# 3_Buck_Boost_19V.net
KiCad netlist of a schematic drawn in Altium Designer
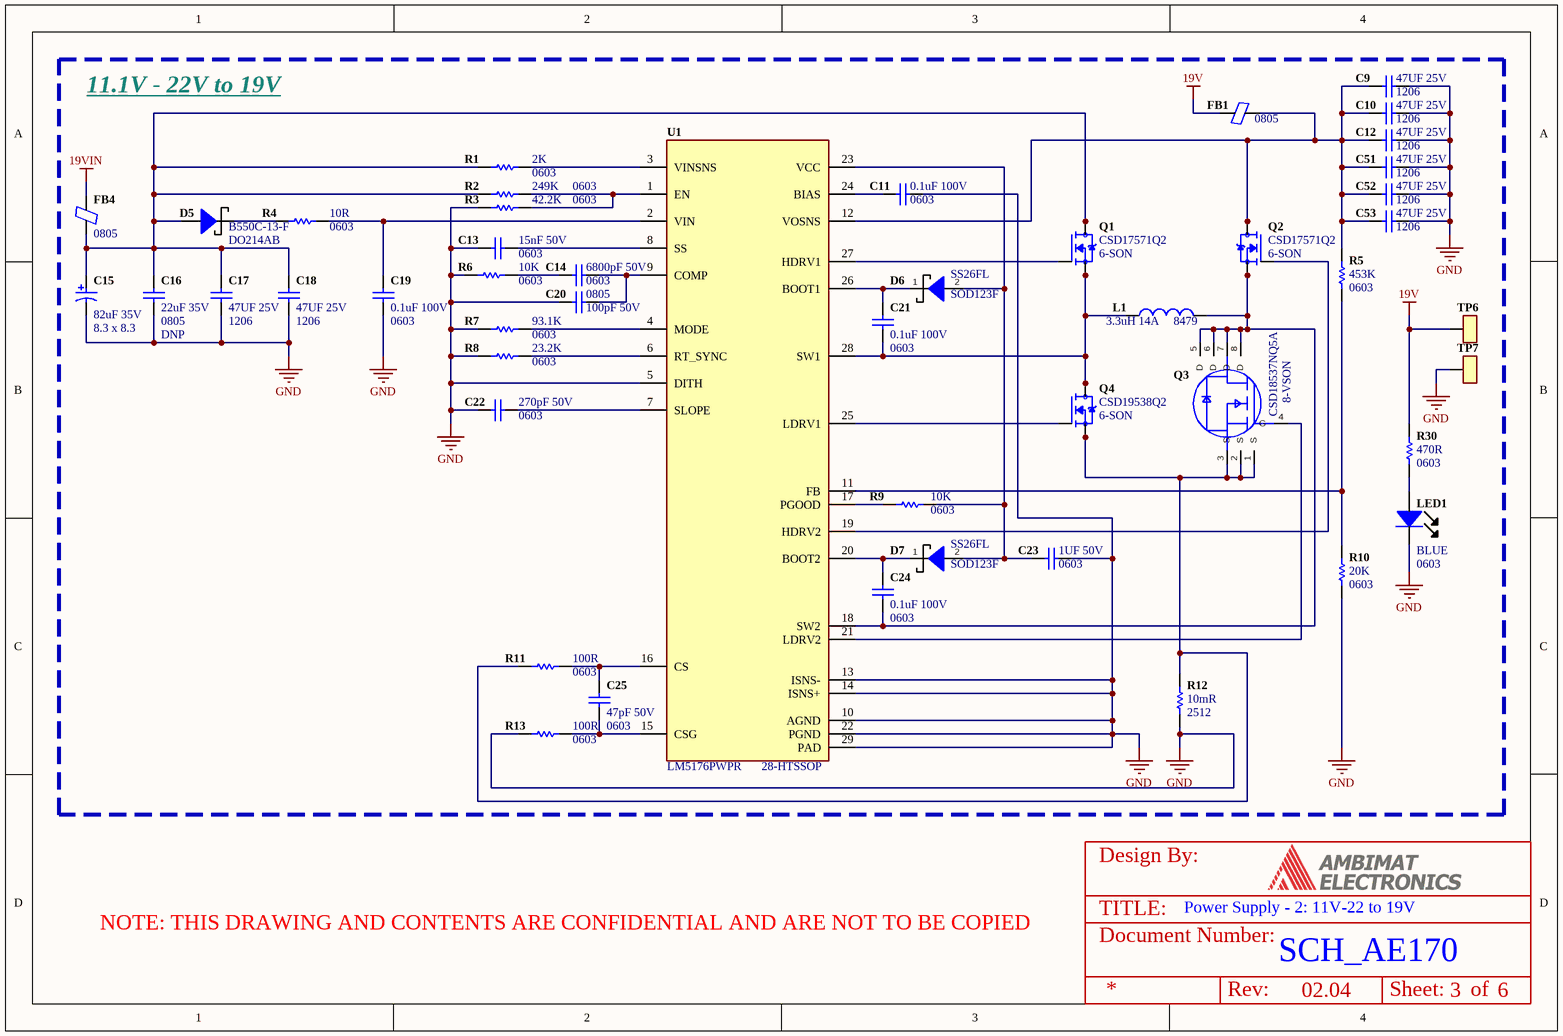
[diagram p0: 3. Buck Boost_19V.SchDoc]

(export (version "E")
  (design (tool "Eeschema 10.0.6"))
  (components
    (comp (ref "C9")
      (value "CAP CER 47UF 25V X5R 1206")
      (footprint "LimLabDL:1206 - NP")
      (fields
        (field (name "MANUFACTURER PART NUMBER") "C3216X5R1E476M160AC")
        (field (name "MANUFACTURER") "TDK Corporation")
        (field (name "VENDOR-1 PART NUMBER") "445-8047-1-ND")
        (field (name "PART NAME") "47UF 25V")
        (field (name "PCB FOOTPRINT") "1206")
      )
      (libsource (lib "LimLabDL") (part "CS47UF-25V1206"))
    )
    (comp (ref "C10")
      (value "CAP CER 47UF 25V X5R 1206")
      (footprint "LimLabDL:1206 - NP")
      (fields
        (field (name "MANUFACTURER PART NUMBER") "C3216X5R1E476M160AC")
        (field (name "MANUFACTURER") "TDK Corporation")
        (field (name "VENDOR-1 PART NUMBER") "445-8047-1-ND")
        (field (name "PART NAME") "47UF 25V")
        (field (name "PCB FOOTPRINT") "1206")
      )
      (libsource (lib "LimLabDL") (part "CS47UF-25V1206"))
    )
    (comp (ref "C11")
      (value "CAP CER 0.1UF 100V X7R 0603")
      (footprint "LimLabDL:0603C")
      (fields
        (field (name "MANU PART NUMBER") "CC0603KRX7R0BB104")
        (field (name "MANUFACTURER") "YAGEO")
        (field (name "PART NAME") "0.1uF 100V")
        (field (name "PCB FOOTPRINT") "0603")
        (field (name "VENDOR-1 PART NUMBER") "311-1523-1-ND")
      )
      (libsource (lib "LimLabDL") (part "CS0.1uF-100V0603"))
    )
    (comp (ref "C12")
      (value "CAP CER 47UF 25V X5R 1206")
      (footprint "LimLabDL:1206 - NP")
      (fields
        (field (name "MANUFACTURER PART NUMBER") "C3216X5R1E476M160AC")
        (field (name "MANUFACTURER") "TDK Corporation")
        (field (name "VENDOR-1 PART NUMBER") "445-8047-1-ND")
        (field (name "PART NAME") "47UF 25V")
        (field (name "PCB FOOTPRINT") "1206")
      )
      (libsource (lib "LimLabDL") (part "CS47UF-25V1206"))
    )
    (comp (ref "C13")
      (value "CAP CER 0.015UF 50V X7R 0603")
      (footprint "LimLabDL:0603C")
      (fields
        (field (name "MANUFACTURER PART NUMBER") "CL10B153KB8NNNC")
        (field (name "MANUFACTURER") "Samsung Electro-Mechanics")
        (field (name "VENDOR-1 PART NUMBER") "1276-1277-1-ND")
        (field (name "PART NAME") "15nF 50V")
        (field (name "PCB FOOTPRINT") "0603")
      )
      (libsource (lib "LimLabDL") (part "CS15nF-50V0603"))
    )
    (comp (ref "C14")
      (value "CAP CER 6800PF 50V X7R 0603")
      (footprint "LimLabDL:0603C")
      (fields
        (field (name "MANUFACTURER") "YAGEO")
        (field (name "VENDOR-1 PART NUMBER") "13-AC0603KPX7R9BB682CT-ND")
        (field (name "PART NAME") "6800pF 50V")
        (field (name "PCB FOOTPRINT") "0603")
        (field (name "MANUFACTURER PART NUMBER") "AC0603KPX7R9BB682")
      )
      (libsource (lib "LimLabDL") (part "CS6800pF-50V0603"))
    )
    (comp (ref "C15")
      (value "CAP ALUM POLY 82UF 20% 35V SMD")
      (footprint "LimLabDL:CAP_PC_8X12_NCH")
      (fields
        (field (name "MANU PART NUMBER") "35SVPF82M")
        (field (name "MANUFACTURER") "Panasonic")
        (field (name "VENDOR-1 PART NUMBER") "P16562CT-ND")
        (field (name "PART NAME") "82uF 35V")
        (field (name "PCB FOOTPRINT") "8.3 x 8.3")
      )
      (libsource (lib "LimLabDL") (part "CS82uF-35VALUM"))
    )
    (comp (ref "C16")
      (value "CAP CER 22UF 35V X5R 0805")
      (footprint "LimLabDL:0805C")
      (fields
        (field (name "MANU PART NUMBER") "C2012X5R1V226M125AC")
        (field (name "MANUFACTURER") "TDK Corporation")
        (field (name "MOUNTING") "DNP")
        (field (name "VENDOR-1 PART NUMBER") "445-14428-1-ND")
        (field (name "PART NAME") "22uF 35V")
        (field (name "PCB FOOTPRINT") "0805")
      )
      (libsource (lib "LimLabDL") (part "CS22uF-35V0805"))
    )
    (comp (ref "C17")
      (value "CAP CER 47UF 25V X5R 1206")
      (footprint "LimLabDL:1206 - NP")
      (fields
        (field (name "MANUFACTURER PART NUMBER") "C3216X5R1E476M160AC")
        (field (name "MANUFACTURER") "TDK Corporation")
        (field (name "VENDOR-1 PART NUMBER") "445-8047-1-ND")
        (field (name "PART NAME") "47UF 25V")
        (field (name "PCB FOOTPRINT") "1206")
      )
      (libsource (lib "LimLabDL") (part "CS47UF-25V1206"))
    )
    (comp (ref "C18")
      (value "CAP CER 47UF 25V X5R 1206")
      (footprint "LimLabDL:1206 - NP")
      (fields
        (field (name "MANUFACTURER PART NUMBER") "C3216X5R1E476M160AC")
        (field (name "MANUFACTURER") "TDK Corporation")
        (field (name "VENDOR-1 PART NUMBER") "445-8047-1-ND")
        (field (name "PART NAME") "47UF 25V")
        (field (name "PCB FOOTPRINT") "1206")
      )
      (libsource (lib "LimLabDL") (part "CS47UF-25V1206"))
    )
    (comp (ref "C19")
      (value "CAP CER 0.1UF 100V X7R 0603")
      (footprint "LimLabDL:0603C")
      (fields
        (field (name "MANU PART NUMBER") "CC0603KRX7R0BB104")
        (field (name "MANUFACTURER") "YAGEO")
        (field (name "PART NAME") "0.1uF 100V")
        (field (name "PCB FOOTPRINT") "0603")
        (field (name "VENDOR-1 PART NUMBER") "311-1523-1-ND")
      )
      (libsource (lib "LimLabDL") (part "CS0.1uF-100V0603"))
    )
    (comp (ref "C20")
      (value "CAP CER 100PF 50V C0G/NP0 0805")
      (footprint "LimLabDL:0805C")
      (fields
        (field (name "MANUFACTURER") "AVX Corporation")
        (field (name "VENDOR-1 PART NUMBER") "478-1316-1-ND")
        (field (name "PART NAME") "100pF 50V")
        (field (name "PCB FOOTPRINT") "0805")
        (field (name "MANU PART NUMBER") "08055A101JAT2A")
      )
      (libsource (lib "LimLabDL") (part "CS100pF-50V0805"))
    )
    (comp (ref "C21")
      (value "CAP CER 0.1UF 100V X7R 0603")
      (footprint "LimLabDL:0603C")
      (fields
        (field (name "MANU PART NUMBER") "CC0603KRX7R0BB104")
        (field (name "MANUFACTURER") "YAGEO")
        (field (name "PART NAME") "0.1uF 100V")
        (field (name "PCB FOOTPRINT") "0603")
        (field (name "VENDOR-1 PART NUMBER") "311-1523-1-ND")
      )
      (libsource (lib "LimLabDL") (part "CS0.1uF-100V0603"))
    )
    (comp (ref "C22")
      (value "CAP CER 270PF 50V X7R 0603")
      (footprint "LimLabDL:0603C")
      (fields
        (field (name "MANUFACTURER PART NUMBER") "CC0603KRX7R9BB271")
        (field (name "MANUFACTURER") "Yageo")
        (field (name "VENDOR-1 PART NUMBER") "311-1185-1-ND")
        (field (name "PART NAME") "270pF 50V")
        (field (name "PCB FOOTPRINT") "0603")
      )
      (libsource (lib "LimLabDL") (part "CS270pF-50V0603"))
    )
    (comp (ref "C23")
      (value "CAP CER 1UF 50V X7R 0603")
      (footprint "LimLabDL:0603C")
      (fields
        (field (name "MANU PART NUMBER") "CC0603KRX7R9BB105")
        (field (name "MANUFACTURER") "Yageo")
        (field (name "PART NAME") "1UF 50V")
        (field (name "PCB FOOTPRINT") "0603")
        (field (name "VENDOR-1 PART NUMBER") "311-2082-1-ND")
      )
      (libsource (lib "LimLabDL") (part "CS1uF-50V0603"))
    )
    (comp (ref "C24")
      (value "CAP CER 0.1UF 100V X7R 0603")
      (footprint "LimLabDL:0603C")
      (fields
        (field (name "MANU PART NUMBER") "CC0603KRX7R0BB104")
        (field (name "MANUFACTURER") "YAGEO")
        (field (name "PART NAME") "0.1uF 100V")
        (field (name "PCB FOOTPRINT") "0603")
        (field (name "VENDOR-1 PART NUMBER") "311-1523-1-ND")
      )
      (libsource (lib "LimLabDL") (part "CS0.1uF-100V0603"))
    )
    (comp (ref "C25")
      (value "CAP CER 47PF 50V X7R 10% 0603")
      (footprint "LimLabDL:0603C")
      (fields
        (field (name "MANUFACTURER") "KEMET")
        (field (name "VENDOR-1 PART NUMBER") "399-16402-1-ND")
        (field (name "PART NAME") "47pF 50V")
        (field (name "PCB FOOTPRINT") "0603")
        (field (name "MANUFACTURER PART NUMBER") "C0603C470K5RAC7867")
      )
      (libsource (lib "LimLabDL") (part "CS47pF-50V0603"))
    )
    (comp (ref "C51")
      (value "CAP CER 47UF 25V X5R 1206")
      (footprint "LimLabDL:1206 - NP")
      (fields
        (field (name "MANUFACTURER PART NUMBER") "C3216X5R1E476M160AC")
        (field (name "MANUFACTURER") "TDK Corporation")
        (field (name "VENDOR-1 PART NUMBER") "445-8047-1-ND")
        (field (name "PART NAME") "47UF 25V")
        (field (name "PCB FOOTPRINT") "1206")
      )
      (libsource (lib "LimLabDL") (part "CS47UF-25V1206"))
    )
    (comp (ref "C52")
      (value "CAP CER 47UF 25V X5R 1206")
      (footprint "LimLabDL:1206 - NP")
      (fields
        (field (name "MANUFACTURER PART NUMBER") "C3216X5R1E476M160AC")
        (field (name "MANUFACTURER") "TDK Corporation")
        (field (name "VENDOR-1 PART NUMBER") "445-8047-1-ND")
        (field (name "PART NAME") "47UF 25V")
        (field (name "PCB FOOTPRINT") "1206")
      )
      (libsource (lib "LimLabDL") (part "CS47UF-25V1206"))
    )
    (comp (ref "C53")
      (value "CAP CER 47UF 25V X5R 1206")
      (footprint "LimLabDL:1206 - NP")
      (fields
        (field (name "MANUFACTURER PART NUMBER") "C3216X5R1E476M160AC")
        (field (name "MANUFACTURER") "TDK Corporation")
        (field (name "VENDOR-1 PART NUMBER") "445-8047-1-ND")
        (field (name "PART NAME") "47UF 25V")
        (field (name "PCB FOOTPRINT") "1206")
      )
      (libsource (lib "LimLabDL") (part "CS47UF-25V1206"))
    )
    (comp (ref "D5")
      (value "DIODE SCHOTTKY 50V 5A SMC")
      (footprint "LimLabDL:DO-214AB-SHKY")
      (fields
        (field (name "MANU PART NUMBER") "B550C-13-F")
        (field (name "MANUFACTURER") "Diodes Incorporated")
        (field (name "VENDOR-1 PART NUMBER") "B550C-FDICT-ND")
        (field (name "PCB FOOTPRINT") "DO214AB")
        (field (name "PART NAME") "B550C-13-F")
      )
      (libsource (lib "LimLabDL") (part "DS-B550C-13-F"))
    )
    (comp (ref "D6")
      (value "DIODE SCHOTTKY 60V 2A SOD123F")
      (footprint "LimLabDL:SOD123F-SHKY")
      (fields
        (field (name "MANU PART NUMBER") "SS26FL")
        (field (name "MANUFACTURER") "onsemi")
        (field (name "VENDOR-1 PART NUMBER") "SS26FLCT-ND")
        (field (name "PCB FOOTPRINT") "SOD123F")
        (field (name "PART NAME") "SS26FL")
      )
      (libsource (lib "LimLabDL") (part "DS-SS26FL"))
    )
    (comp (ref "D7")
      (value "DIODE SCHOTTKY 60V 2A SOD123F")
      (footprint "LimLabDL:SOD123F-SHKY")
      (fields
        (field (name "MANU PART NUMBER") "SS26FL")
        (field (name "MANUFACTURER") "onsemi")
        (field (name "VENDOR-1 PART NUMBER") "SS26FLCT-ND")
        (field (name "PCB FOOTPRINT") "SOD123F")
        (field (name "PART NAME") "SS26FL")
      )
      (libsource (lib "LimLabDL") (part "DS-SS26FL"))
    )
    (comp (ref "FB1")
      (value "FERRITE BEAD 120 OHM 0805 1LN")
      (footprint "LimLabDL:0805F")
      (fields
        (field (name "MANUFACTURER") "Pulse Electronics")
        (field (name "MANUFACTURER PART NUMBER") "ABUP00201209121Y00")
        (field (name "VENDOR-1 PART NUMBER") "553-ABUP00201209121Y00CT-ND")
        (field (name "PCB FOOTPRINT") "0805")
      )
      (libsource (lib "LimLabDL") (part "FB120OHM-0805"))
    )
    (comp (ref "FB4")
      (value "FERRITE BEAD 120 OHM 0805 1LN")
      (footprint "LimLabDL:0805F")
      (fields
        (field (name "MANUFACTURER") "Pulse Electronics")
        (field (name "MANUFACTURER PART NUMBER") "ABUP00201209121Y00")
        (field (name "VENDOR-1 PART NUMBER") "553-ABUP00201209121Y00CT-ND")
        (field (name "PCB FOOTPRINT") "0805")
      )
      (libsource (lib "LimLabDL") (part "FB120OHM-0805"))
    )
    (comp (ref "L1")
      (value "FIXED IND 3.3UH 14A 8.2 MOHM SMD")
      (footprint "LimLabDL:IND_8070-WE")
      (fields
        (field (name "MANUFACTURER PART NUMBER") "7443340330")
        (field (name "MANUFACTURER") "Würth Elektronik")
        (field (name "VENDOR-1 PART NUMBER") "732-2165-1-ND")
        (field (name "PART NAME") "3.3uH 14A")
        (field (name "PCB FOOTPRINT") "8479")
      )
      (libsource (lib "LimLabDL") (part "LS3.3uH14A-8479"))
    )
    (comp (ref "LED1")
      (value "LB Q39G-L2N2-35-1")
      (footprint "LimLabDL:LED0603_BLUE")
      (description "LED BLUE CLEAR 3MM 470NM")
      (fields
        (field (name "MANUFACTURER") "OSRAM Opto Semiconductors Inc")
        (field (name "VENDOR-1 PART NUMBER") "475-2816-1-ND")
        (field (name "PCB FOOTPRINT") "0603")
        (field (name "COLOR") "BLUE")
      )
      (libsource (lib "LimLabDL") (part "LED-BLUE0603"))
    )
    (comp (ref "Q1")
      (value "MOSFET N-CH 30V 22A 6SON")
      (footprint "LimLabDL:CSD17571Q2")
      (fields
        (field (name "MANU PART NUMBER") "CSD17571Q2")
        (field (name "MANUFACTURER") "Texas Instruments")
        (field (name "VENDOR-1 PART NUMBER") "296-37193-1-ND")
        (field (name "PCB FOOTPRINT") "6-SON")
        (field (name "PART NAME") "CSD17571Q2")
      )
      (libsource (lib "LimLabDL") (part "MS-CSD17571Q2"))
    )
    (comp (ref "Q2")
      (value "MOSFET N-CH 30V 22A 6SON")
      (footprint "LimLabDL:CSD17571Q2")
      (fields
        (field (name "MANU PART NUMBER") "CSD17571Q2")
        (field (name "MANUFACTURER") "Texas Instruments")
        (field (name "VENDOR-1 PART NUMBER") "296-37193-1-ND")
        (field (name "PCB FOOTPRINT") "6-SON")
        (field (name "PART NAME") "CSD17571Q2")
      )
      (libsource (lib "LimLabDL") (part "MS-CSD17571Q2"))
    )
    (comp (ref "Q3")
      (value "MOSFET N-CH 60V 50A 8VSON")
      (footprint "LimLabDL:SON127P500X600")
      (fields
        (field (name "MANU PART NUMBER") "CSD18537NQ5A")
        (field (name "MANUFACTURER") "Texas Instruments")
        (field (name "VENDOR-1 PART NUMBER") "296-36455-1-ND")
        (field (name "PCB FOOTPRINT") "8-VSON")
        (field (name "PART NAME") "CSD18537NQ5A")
      )
      (libsource (lib "LimLabDL") (part "MS-CSD18537NQ5A"))
    )
    (comp (ref "Q4")
      (value "MOSFET N-CH 100V 14.4A 6WSON")
      (footprint "LimLabDL:CSD17571Q2")
      (fields
        (field (name "MANU PART NUMBER") "CSD19538Q2")
        (field (name "MANUFACTURER") "Texas Instruments")
        (field (name "VENDOR-1 PART NUMBER") "296-37193-1-ND")
        (field (name "PCB FOOTPRINT") "6-SON")
        (field (name "PART NAME") "CSD19538Q2")
      )
      (libsource (lib "LimLabDL") (part "MS-CSD19538Q2"))
    )
    (comp (ref "R1")
      (value "RS2K-0.1W0603")
      (footprint "LimLabDL:0603")
      (description "RES SMD 2K OHM 5% 1/10W 0603")
      (fields
        (field (name "MANU PART NUMBER") "ERJ-3GEYJ202V")
        (field (name "MANUFACTURER") "Panasonic")
        (field (name "PART NAME") "2K")
        (field (name "PCB FOOTPRINT") "0603")
      )
      (libsource (lib "LimLabDL") (part "RS2K-0.1W0603"))
    )
    (comp (ref "R2")
      (value "RES SMD 249K OHM 1% 1/10W 0603")
      (footprint "LimLabDL:0603")
      (fields
        (field (name "MANUFACTURER PART NUMBER") "AC0603FR-07249KL")
        (field (name "MANUFACTURER") "Yageo")
        (field (name "VENDOR-1 PART NUMBER") "13-AC0603FR-07249KLCT-ND")
        (field (name "PART NAME") "249K")
        (field (name "PCB FOOTPRINT") "0603")
      )
      (libsource (lib "LimLabDL") (part "RS249K-0.1W0603"))
    )
    (comp (ref "R3")
      (value "RES 42.2K OHM 1% 1/10W 0603")
      (footprint "LimLabDL:0603")
      (fields
        (field (name "MANUFACTURER PART NUMBER") "RC0603FR-0742K2L")
        (field (name "MANUFACTURER") "Yageo")
        (field (name "VENDOR-1 PART NUMBER") "311-42.2KHRCT-ND")
        (field (name "PART NAME") "42.2K")
        (field (name "PCB FOOTPRINT") "0603")
      )
      (libsource (lib "LimLabDL") (part "RS42.2K-0.1W0603"))
    )
    (comp (ref "R4")
      (value "RES SMD 10 OHM 1% 1/10W 0603")
      (footprint "LimLabDL:0603")
      (fields
        (field (name "MANU PART NUMBER") "CRCW060310R0FKEA")
        (field (name "MANUFACTURER") "Vishay Dale")
        (field (name "VENDOR-1 PART NUMBER") "541-10.0HCT-ND")
        (field (name "PART NAME") "10R")
        (field (name "PCB FOOTPRINT") "0603")
      )
      (libsource (lib "LimLabDL") (part "RS10R-0.1W0603"))
    )
    (comp (ref "R5")
      (value "RES 453K OHM 1% 1/10W 0603")
      (footprint "LimLabDL:0603")
      (fields
        (field (name "MANU PART NUMBER") "RC0603FR-07453KL")
        (field (name "MANUFACTURER") "Yageo")
        (field (name "VENDOR-1 PART NUMBER") "311-453KHRCT-ND")
        (field (name "PART NAME") "453K")
        (field (name "PCB FOOTPRINT") "0603")
      )
      (libsource (lib "LimLabDL") (part "RS453K-0.1W0603"))
    )
    (comp (ref "R6")
      (value "RES SMD 10K OHM 5% 1/10W 0603")
      (footprint "LimLabDL:0603")
      (fields
        (field (name "MANUFACTURER PART NUMBER") "RC0603JR-0710KL")
        (field (name "MANUFACTURER") "Yageo")
        (field (name "VENDOR-1 PART NUMBER") "311-10KGRCT-ND")
        (field (name "PART NAME") "10K")
        (field (name "PCB FOOTPRINT") "0603")
      )
      (libsource (lib "LimLabDL") (part "RS10K-0.1W0603"))
    )
    (comp (ref "R7")
      (value "RES 93.1K OHM 1% 1/10W 0603")
      (footprint "LimLabDL:0603")
      (fields
        (field (name "MANU PART NUMBER") "RC0603FR-0793K1L")
        (field (name "MANUFACTURER") "YAGEO")
        (field (name "VENDOR-1 PART NUMBER") "311-93.1KHRCT-ND")
        (field (name "PART NAME") "93.1K")
        (field (name "PCB FOOTPRINT") "0603")
      )
      (libsource (lib "LimLabDL") (part "RS93.1K-0.1W0603"))
    )
    (comp (ref "R8")
      (value "RES 23.2K OHM 1% 1/10W 0603")
      (footprint "LimLabDL:0603")
      (fields
        (field (name "MANU PART NUMBER") "RC0603FR-0723K2L")
        (field (name "MANUFACTURER") "YAGEO")
        (field (name "VENDOR-1 PART NUMBER") "311-23.2KHRCT-ND")
        (field (name "PART NAME") "23.2K")
        (field (name "PCB FOOTPRINT") "0603")
      )
      (libsource (lib "LimLabDL") (part "RS23.2K-0.1W0603"))
    )
    (comp (ref "R9")
      (value "RES SMD 10K OHM 5% 1/10W 0603")
      (footprint "LimLabDL:0603")
      (fields
        (field (name "MANUFACTURER") "Yageo")
        (field (name "VENDOR-1 PART NUMBER") "311-10KGRCT-ND")
        (field (name "PCB FOOTPRINT") "0603")
        (field (name "PART NAME") "10K")
        (field (name "MANUFACTURER PART NUMBER") "RC0603JR-0710KL")
      )
      (libsource (lib "LimLabDL") (part "RS10K-0.1W0603"))
    )
    (comp (ref "R10")
      (value "RES SMD 20K OHM 5% 1/10W 0603")
      (footprint "LimLabDL:0603")
      (fields
        (field (name "MANU PART NUMBER") "CRCW060320K0JNEA")
        (field (name "MANUFACTURER") "Vishay Dale")
        (field (name "VENDOR-1 PART NUMBER") "541-20KGCT-ND")
        (field (name "PCB FOOTPRINT") "0603")
        (field (name "PART NAME") "20K")
      )
      (libsource (lib "LimLabDL") (part "RS20K-0.1W0603"))
    )
    (comp (ref "R11")
      (value "RES SMD 100 OHM 1% 1/10W 0603")
      (footprint "LimLabDL:0603")
      (fields
        (field (name "MANU PART NUMBER") "CRCW0603100RFKEA")
        (field (name "MANUFACTURER") "Vishay Dale")
        (field (name "VENDOR-1 PART NUMBER") "541-100HCT-ND")
        (field (name "PCB FOOTPRINT") "0603")
        (field (name "PART NAME") "100R")
      )
      (libsource (lib "LimLabDL") (part "RS100R-0.1W0603"))
    )
    (comp (ref "R12")
      (value "RES 0.01 OHM 1% 3W 2512")
      (footprint "LimLabDL:R2512")
      (fields
        (field (name "MANU PART NUMBER") "PA2512FKE7T0R01E")
        (field (name "MANUFACTURER") "YAGEO")
        (field (name "VENDOR-1 PART NUMBER") "13-PA2512FKE7T0R01ECT-ND")
        (field (name "PART NAME") "10mR")
        (field (name "PCB FOOTPRINT") "2512")
      )
      (libsource (lib "LimLabDL") (part "RS10mR-3W2512"))
    )
    (comp (ref "R13")
      (value "RES SMD 100 OHM 1% 1/10W 0603")
      (footprint "LimLabDL:0603")
      (fields
        (field (name "MANU PART NUMBER") "CRCW0603100RFKEA")
        (field (name "MANUFACTURER") "Vishay Dale")
        (field (name "VENDOR-1 PART NUMBER") "541-100HCT-ND")
        (field (name "PCB FOOTPRINT") "0603")
        (field (name "PART NAME") "100R")
      )
      (libsource (lib "LimLabDL") (part "RS100R-0.1W0603"))
    )
    (comp (ref "R30")
      (value "RES 470 OHM 1/10W 5% 0603 SMD")
      (footprint "LimLabDL:0603")
      (fields
        (field (name "MANU PART NUMBER") "RC0603JR-07470RL")
        (field (name "MANUFACTURER") "YAGEO")
        (field (name "VENDOR-1 PART NUMBER") "311-470GRCT-ND")
        (field (name "PART NAME") "470R")
        (field (name "PCB FOOTPRINT") "0603")
      )
      (libsource (lib "LimLabDL") (part "RS470R-1/10W0603"))
    )
    (comp (ref "TP6")
      (value "TEST POINT")
      (footprint "LimLabDL:TP-1.5mmSMD")
      (description "SMD TEST POINT")
      (libsource (lib "LimLabDL") (part "TP-1.5mmSMD"))
    )
    (comp (ref "TP7")
      (value "TEST POINT")
      (footprint "LimLabDL:TP-1.5mmSMD")
      (description "SMD TEST POINT")
      (libsource (lib "LimLabDL") (part "TP-1.5mmSMD"))
    )
    (comp (ref "U1")
      (value "LM5176PWPR")
      (footprint "LimLabDL:HSSOP-28")
      (fields
        (field (name "MANUFACTURER") "Texas Instruments")
        (field (name "VENDOR-1 PART NUMBER") "296-49223-1-ND")
        (field (name "MANUFACTURER PART NUMBE") "LM5176PWPR")
        (field (name "PCB FOOTPRINT") "28-HTSSOP")
      )
      (libsource (lib "LimLabDL") (part "IC28P-LM5176PWPR"))
    )
  )
  (nets
    (net (code "1") (name "19V") (class "Default")
      (node (ref "FB1") (pin "1") (pinfunction "1_1") (pintype "passive"))
      (node (ref "R30") (pin "2") (pinfunction "2_2") (pintype "passive"))
      (node (ref "TP6") (pin "1") (pinfunction "1_1") (pintype "passive"))
    )
    (net (code "2") (name "19VIN") (class "Default")
      (node (ref "FB4") (pin "1") (pinfunction "1_1") (pintype "passive"))
    )
    (net (code "3") (name "GND") (class "Default")
      (node (ref "C10") (pin "2") (pinfunction "2_2") (pintype "passive"))
      (node (ref "C11") (pin "2") (pinfunction "2_2") (pintype "passive"))
      (node (ref "C12") (pin "2") (pinfunction "2_2") (pintype "passive"))
      (node (ref "C13") (pin "1") (pinfunction "1_1") (pintype "passive"))
      (node (ref "C15") (pin "2") (pinfunction "2_2") (pintype "passive"))
      (node (ref "C16") (pin "2") (pinfunction "2_2") (pintype "passive"))
      (node (ref "C17") (pin "1") (pinfunction "1_1") (pintype "passive"))
      (node (ref "C18") (pin "1") (pinfunction "1_1") (pintype "passive"))
      (node (ref "C19") (pin "2") (pinfunction "2_2") (pintype "passive"))
      (node (ref "C20") (pin "1") (pinfunction "1_1") (pintype "passive"))
      (node (ref "C22") (pin "1") (pinfunction "1_1") (pintype "passive"))
      (node (ref "C23") (pin "2") (pinfunction "2_2") (pintype "passive"))
      (node (ref "C51") (pin "2") (pinfunction "2_2") (pintype "passive"))
      (node (ref "C52") (pin "2") (pinfunction "2_2") (pintype "passive"))
      (node (ref "C53") (pin "2") (pinfunction "2_2") (pintype "passive"))
      (node (ref "C9") (pin "2") (pinfunction "2_2") (pintype "passive"))
      (node (ref "LED1") (pin "2") (pinfunction "K_2") (pintype "passive"))
      (node (ref "R10") (pin "1") (pinfunction "1_1") (pintype "passive"))
      (node (ref "R12") (pin "1") (pinfunction "1_1") (pintype "passive"))
      (node (ref "R13") (pin "1") (pinfunction "1_1") (pintype "passive"))
      (node (ref "R3") (pin "1") (pinfunction "1_1") (pintype "passive"))
      (node (ref "R6") (pin "1") (pinfunction "1_1") (pintype "passive"))
      (node (ref "R7") (pin "1") (pinfunction "1_1") (pintype "passive"))
      (node (ref "R8") (pin "1") (pinfunction "1_1") (pintype "passive"))
      (node (ref "TP7") (pin "1") (pinfunction "1_1") (pintype "passive"))
      (node (ref "U1") (pin "10") (pinfunction "AGND_10") (pintype "passive"))
      (node (ref "U1") (pin "13") (pinfunction "ISNS-_13") (pintype "passive"))
      (node (ref "U1") (pin "14") (pinfunction "ISNS+_14") (pintype "passive"))
      (node (ref "U1") (pin "22") (pinfunction "PGND_22") (pintype "passive"))
      (node (ref "U1") (pin "29") (pinfunction "PAD_29") (pintype "passive"))
      (node (ref "U1") (pin "5") (pinfunction "DITH_5") (pintype "passive"))
    )
    (net (code "4") (name "Net-(C14-Pad1)") (class "Default")
      (node (ref "C14") (pin "1") (pinfunction "1_1") (pintype "passive"))
      (node (ref "R6") (pin "2") (pinfunction "2_2") (pintype "passive"))
    )
    (net (code "5") (name "Net-(C15-Pad1)") (class "Default")
      (node (ref "C15") (pin "1") (pinfunction "1_1") (pintype "passive"))
      (node (ref "C16") (pin "1") (pinfunction "1_1") (pintype "passive"))
      (node (ref "C17") (pin "2") (pinfunction "2_2") (pintype "passive"))
      (node (ref "C18") (pin "2") (pinfunction "2_2") (pintype "passive"))
      (node (ref "D5") (pin "2") (pinfunction "2_2") (pintype "passive"))
      (node (ref "FB4") (pin "2") (pinfunction "2_2") (pintype "passive"))
      (node (ref "Q1") (pin "1") (pinfunction "D_1") (pintype "passive"))
      (node (ref "Q1") (pin "2") (pinfunction "D_2") (pintype "passive"))
      (node (ref "Q1") (pin "5") (pinfunction "D_5") (pintype "passive"))
      (node (ref "Q1") (pin "6") (pinfunction "D_6") (pintype "passive"))
      (node (ref "Q1") (pin "7") (pinfunction "D_7") (pintype "passive"))
      (node (ref "R1") (pin "1") (pinfunction "1_1") (pintype "passive"))
      (node (ref "R2") (pin "1") (pinfunction "1_1") (pintype "passive"))
    )
    (net (code "6") (name "Net-(D5-Pad1)") (class "Default")
      (node (ref "D5") (pin "1") (pinfunction "1_1") (pintype "passive"))
      (node (ref "R4") (pin "1") (pinfunction "1_1") (pintype "passive"))
    )
    (net (code "7") (name "Net-(LED1-A)") (class "Default")
      (node (ref "LED1") (pin "1") (pinfunction "A_1") (pintype "passive"))
      (node (ref "R30") (pin "1") (pinfunction "1_1") (pintype "passive"))
    )
    (net (code "8") (name "Net-(Q1-G)") (class "Default")
      (node (ref "Q1") (pin "3") (pinfunction "G_3") (pintype "passive"))
      (node (ref "U1") (pin "27") (pinfunction "HDRV1_27") (pintype "passive"))
    )
    (net (code "9") (name "Net-(Q2-G)") (class "Default")
      (node (ref "Q2") (pin "3") (pinfunction "G_3") (pintype "passive"))
      (node (ref "U1") (pin "19") (pinfunction "HDRV2_19") (pintype "passive"))
    )
    (net (code "10") (name "Net-(Q3-G)") (class "Default")
      (node (ref "Q3") (pin "4") (pinfunction "G_4") (pintype "passive"))
      (node (ref "U1") (pin "21") (pinfunction "LDRV2_21") (pintype "passive"))
    )
    (net (code "11") (name "Net-(Q3-S-Pad1)") (class "Default")
      (node (ref "Q3") (pin "1") (pinfunction "S_1") (pintype "passive"))
      (node (ref "Q3") (pin "2") (pinfunction "S_2") (pintype "passive"))
      (node (ref "Q3") (pin "3") (pinfunction "S_3") (pintype "passive"))
      (node (ref "Q4") (pin "4") (pinfunction "S_4") (pintype "passive"))
      (node (ref "Q4") (pin "8") (pinfunction "S_8") (pintype "passive"))
      (node (ref "R11") (pin "1") (pinfunction "1_1") (pintype "passive"))
      (node (ref "R12") (pin "2") (pinfunction "2_2") (pintype "passive"))
    )
    (net (code "12") (name "Net-(Q4-G)") (class "Default")
      (node (ref "Q4") (pin "3") (pinfunction "G_3") (pintype "passive"))
      (node (ref "U1") (pin "25") (pinfunction "LDRV1_25") (pintype "passive"))
    )
    (net (code "13") (name "Net-(U1-BIAS)") (class "Default")
      (node (ref "C11") (pin "1") (pinfunction "1_1") (pintype "passive"))
      (node (ref "U1") (pin "24") (pinfunction "BIAS_24") (pintype "passive"))
    )
    (net (code "14") (name "Net-(U1-BOOT1)") (class "Default")
      (node (ref "C21") (pin "2") (pinfunction "2_2") (pintype "passive"))
      (node (ref "D6") (pin "1") (pinfunction "1_1") (pintype "passive"))
      (node (ref "U1") (pin "26") (pinfunction "BOOT1_26") (pintype "passive"))
    )
    (net (code "15") (name "Net-(U1-BOOT2)") (class "Default")
      (node (ref "C24") (pin "2") (pinfunction "2_2") (pintype "passive"))
      (node (ref "D7") (pin "1") (pinfunction "1_1") (pintype "passive"))
      (node (ref "U1") (pin "20") (pinfunction "BOOT2_20") (pintype "passive"))
    )
    (net (code "16") (name "Net-(U1-COMP)") (class "Default")
      (node (ref "C14") (pin "2") (pinfunction "2_2") (pintype "passive"))
      (node (ref "C20") (pin "2") (pinfunction "2_2") (pintype "passive"))
      (node (ref "U1") (pin "9") (pinfunction "COMP_9") (pintype "passive"))
    )
    (net (code "17") (name "Net-(U1-CS)") (class "Default")
      (node (ref "C25") (pin "1") (pinfunction "1_1") (pintype "passive"))
      (node (ref "R11") (pin "2") (pinfunction "2_2") (pintype "passive"))
      (node (ref "U1") (pin "16") (pinfunction "CS_16") (pintype "passive"))
    )
    (net (code "18") (name "Net-(U1-CSG)") (class "Default")
      (node (ref "C25") (pin "2") (pinfunction "2_2") (pintype "passive"))
      (node (ref "R13") (pin "2") (pinfunction "2_2") (pintype "passive"))
      (node (ref "U1") (pin "15") (pinfunction "CSG_15") (pintype "passive"))
    )
    (net (code "19") (name "Net-(U1-EN)") (class "Default")
      (node (ref "R2") (pin "2") (pinfunction "2_2") (pintype "passive"))
      (node (ref "R3") (pin "2") (pinfunction "2_2") (pintype "passive"))
      (node (ref "U1") (pin "1") (pinfunction "EN_1") (pintype "passive"))
    )
    (net (code "20") (name "Net-(U1-FB)") (class "Default")
      (node (ref "R10") (pin "2") (pinfunction "2_2") (pintype "passive"))
      (node (ref "R5") (pin "1") (pinfunction "1_1") (pintype "passive"))
      (node (ref "U1") (pin "11") (pinfunction "FB_11") (pintype "passive"))
    )
    (net (code "21") (name "Net-(U1-MODE)") (class "Default")
      (node (ref "R7") (pin "2") (pinfunction "2_2") (pintype "passive"))
      (node (ref "U1") (pin "4") (pinfunction "MODE_4") (pintype "passive"))
    )
    (net (code "22") (name "Net-(U1-PGOOD)") (class "Default")
      (node (ref "R9") (pin "1") (pinfunction "1_1") (pintype "passive"))
      (node (ref "U1") (pin "17") (pinfunction "PGOOD_17") (pintype "passive"))
    )
    (net (code "23") (name "Net-(U1-RT_SYNC)") (class "Default")
      (node (ref "R8") (pin "2") (pinfunction "2_2") (pintype "passive"))
      (node (ref "U1") (pin "6") (pinfunction "RT_SYNC_6") (pintype "passive"))
    )
    (net (code "24") (name "Net-(U1-SLOPE)") (class "Default")
      (node (ref "C22") (pin "2") (pinfunction "2_2") (pintype "passive"))
      (node (ref "U1") (pin "7") (pinfunction "SLOPE_7") (pintype "passive"))
    )
    (net (code "25") (name "Net-(U1-SS)") (class "Default")
      (node (ref "C13") (pin "2") (pinfunction "2_2") (pintype "passive"))
      (node (ref "U1") (pin "8") (pinfunction "SS_8") (pintype "passive"))
    )
    (net (code "26") (name "Net-(U1-SW1)") (class "Default")
      (node (ref "C21") (pin "1") (pinfunction "1_1") (pintype "passive"))
      (node (ref "L1") (pin "1") (pinfunction "1_1") (pintype "passive"))
      (node (ref "Q1") (pin "4") (pinfunction "S_4") (pintype "passive"))
      (node (ref "Q1") (pin "8") (pinfunction "S_8") (pintype "passive"))
      (node (ref "Q4") (pin "1") (pinfunction "D_1") (pintype "passive"))
      (node (ref "Q4") (pin "2") (pinfunction "D_2") (pintype "passive"))
      (node (ref "Q4") (pin "5") (pinfunction "D_5") (pintype "passive"))
      (node (ref "Q4") (pin "6") (pinfunction "D_6") (pintype "passive"))
      (node (ref "Q4") (pin "7") (pinfunction "D_7") (pintype "passive"))
      (node (ref "U1") (pin "28") (pinfunction "SW1_28") (pintype "passive"))
    )
    (net (code "27") (name "Net-(U1-SW2)") (class "Default")
      (node (ref "C24") (pin "1") (pinfunction "1_1") (pintype "passive"))
      (node (ref "L1") (pin "2") (pinfunction "2_2") (pintype "passive"))
      (node (ref "Q2") (pin "4") (pinfunction "S_4") (pintype "passive"))
      (node (ref "Q2") (pin "8") (pinfunction "S_8") (pintype "passive"))
      (node (ref "Q3") (pin "5") (pinfunction "D_5") (pintype "passive"))
      (node (ref "Q3") (pin "6") (pinfunction "D_6") (pintype "passive"))
      (node (ref "Q3") (pin "7") (pinfunction "D_7") (pintype "passive"))
      (node (ref "Q3") (pin "8") (pinfunction "D_8") (pintype "passive"))
      (node (ref "U1") (pin "18") (pinfunction "SW2_18") (pintype "passive"))
    )
    (net (code "28") (name "Net-(U1-VCC)") (class "Default")
      (node (ref "C23") (pin "1") (pinfunction "1_1") (pintype "passive"))
      (node (ref "D6") (pin "2") (pinfunction "2_2") (pintype "passive"))
      (node (ref "D7") (pin "2") (pinfunction "2_2") (pintype "passive"))
      (node (ref "R9") (pin "2") (pinfunction "2_2") (pintype "passive"))
      (node (ref "U1") (pin "23") (pinfunction "VCC_23") (pintype "passive"))
    )
    (net (code "29") (name "Net-(U1-VIN)") (class "Default")
      (node (ref "C19") (pin "1") (pinfunction "1_1") (pintype "passive"))
      (node (ref "R4") (pin "2") (pinfunction "2_2") (pintype "passive"))
      (node (ref "U1") (pin "2") (pinfunction "VIN_2") (pintype "passive"))
    )
    (net (code "30") (name "Net-(U1-VINSNS)") (class "Default")
      (node (ref "R1") (pin "2") (pinfunction "2_2") (pintype "passive"))
      (node (ref "U1") (pin "3") (pinfunction "VINSNS_3") (pintype "passive"))
    )
    (net (code "31") (name "Net-(U1-VOSNS)") (class "Default")
      (node (ref "C10") (pin "1") (pinfunction "1_1") (pintype "passive"))
      (node (ref "C12") (pin "1") (pinfunction "1_1") (pintype "passive"))
      (node (ref "C51") (pin "1") (pinfunction "1_1") (pintype "passive"))
      (node (ref "C52") (pin "1") (pinfunction "1_1") (pintype "passive"))
      (node (ref "C53") (pin "1") (pinfunction "1_1") (pintype "passive"))
      (node (ref "C9") (pin "1") (pinfunction "1_1") (pintype "passive"))
      (node (ref "FB1") (pin "2") (pinfunction "2_2") (pintype "passive"))
      (node (ref "Q2") (pin "1") (pinfunction "D_1") (pintype "passive"))
      (node (ref "Q2") (pin "2") (pinfunction "D_2") (pintype "passive"))
      (node (ref "Q2") (pin "5") (pinfunction "D_5") (pintype "passive"))
      (node (ref "Q2") (pin "6") (pinfunction "D_6") (pintype "passive"))
      (node (ref "Q2") (pin "7") (pinfunction "D_7") (pintype "passive"))
      (node (ref "R5") (pin "2") (pinfunction "2_2") (pintype "passive"))
      (node (ref "U1") (pin "12") (pinfunction "VOSNS_12") (pintype "passive"))
    )
  )
)
